# fram_rtc.net
KiCad netlist of a schematic drawn in Altium Designer
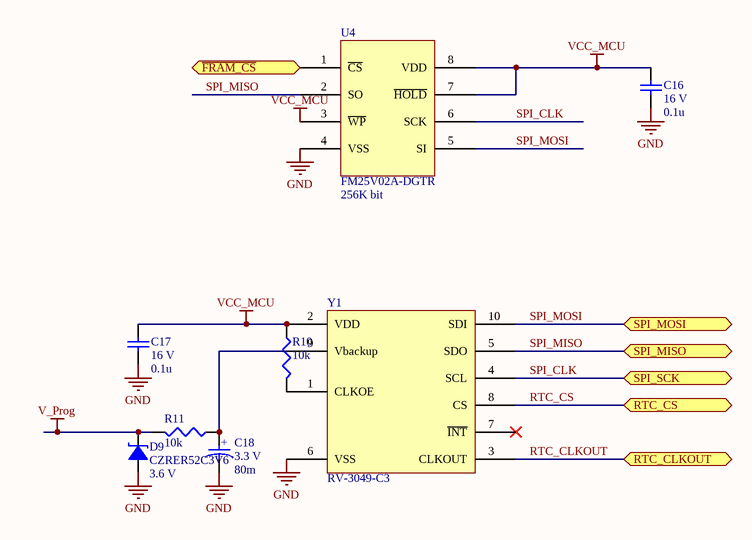
[diagram p0: fram_rtc.SchDoc]

(export (version "E")
  (design (tool "Eeschema 10.0.6"))
  (components
    (comp (ref "C16")
      (value "0.1u")
      (footprint "0402")
      (description "0.10µF ±10% 16V Ceramic Capacitor X7R 0402")
      (fields
        (field (name "VOLTAGE RATED") "16 V")
        (field (name "TOLERANCE") "10%")
        (field (name "MANUFACTURER PART NUMBER") "GRM155R71C104KA88D")
      )
      (libsource (lib "capacitors") (part "GRM155R71C104KA88D"))
    )
    (comp (ref "C17")
      (value "0.1u")
      (footprint "0402")
      (description "0.10µF ±10% 16V Ceramic Capacitor X7R 0402")
      (fields
        (field (name "VOLTAGE RATED") "16 V")
        (field (name "TOLERANCE") "10%")
        (field (name "MANUFACTURER PART NUMBER") "GRM155R71C104KA88D")
      )
      (libsource (lib "capacitors") (part "GRM155R71C104KA88D"))
    )
    (comp (ref "C18")
      (value "80m")
      (footprint "XH414HG-IV01E")
      (description "80mF (EDLC) Supercapacitor 3.3V Coin")
      (fields
        (field (name "VOLTAGE RATED") "3.3 V")
        (field (name "MANUFACTURER PART NUMBER") "XH414HG-IV01E")
      )
      (libsource (lib "capacitors") (part "XH414HG-IV01E"))
    )
    (comp (ref "D9")
      (value "CZRER52C3V6")
      (footprint "0503/SOD-723F")
      (description "Zener Diode 3.6V 150mW ±5% Surface Mount 0503 (1308 Metric)")
      (fields
        (field (name "MANUFACTURER") "Comchip Technology")
        (field (name "POWER") "150 mW")
        (field (name "ZENER VOLTAGE") "3.6 V")
      )
      (libsource (lib "diodes") (part "CZRER52C3V6"))
    )
    (comp (ref "R10")
      (value "10k")
      (footprint "0402")
      (description "RES SMD 10K OHM 1% 1/16W 0402")
      (fields (field (name "TOLERANCE") "1%") (field (name "POWER") "1/16 W"))
      (libsource (lib "resistors") (part "CRCW040210K0FKED"))
    )
    (comp (ref "R11")
      (value "10k")
      (footprint "0402")
      (description "RES SMD 10K OHM 1% 1/16W 0402")
      (fields (field (name "TOLERANCE") "1%") (field (name "POWER") "1/16 W"))
      (libsource (lib "resistors") (part "CRCW040210K0FKED"))
    )
    (comp (ref "U4")
      (value "FM25V02A-DGTR")
      (footprint "TDFN-8")
      (description "256-Kbit (32 K × 8) Serial (SPI) F-RAM")
      (fields (field (name "MANUFACTURER") "Cypress Semiconductor") (field (name "SIZE") "256K bit"))
      (libsource (lib "memory") (part "FM25V02A-DGTR"))
    )
    (comp (ref "Y1")
      (value "RV-3049-C3")
      (footprint "RV-3049-C3")
      (description "Real Time Clock Module with SPI-Bus")
      (libsource (lib "crystal oscillators") (part "RV-3049-C3"))
    )
  )
  (nets
    (net (code "1") (name "/RTC_CLKOUT") (class "Default")
      (node (ref "Y1") (pin "3") (pinfunction "CLKOUT_3") (pintype "passive"))
    )
    (net (code "2") (name "/RTC_CS") (class "Default")
      (node (ref "Y1") (pin "8") (pinfunction "CS_8") (pintype "passive"))
    )
    (net (code "3") (name "/SPI_CLK") (class "Default")
      (node (ref "U4") (pin "6") (pinfunction "SCK_6") (pintype "passive"))
      (node (ref "Y1") (pin "4") (pinfunction "SCL_4") (pintype "passive"))
    )
    (net (code "4") (name "/SPI_MISO") (class "Default")
      (node (ref "U4") (pin "2") (pinfunction "SO_2") (pintype "passive"))
      (node (ref "Y1") (pin "5") (pinfunction "SDO_5") (pintype "passive"))
    )
    (net (code "5") (name "/SPI_MOSI") (class "Default")
      (node (ref "U4") (pin "5") (pinfunction "SI_5") (pintype "passive"))
      (node (ref "Y1") (pin "10") (pinfunction "SDI_10") (pintype "passive"))
    )
    (net (code "6") (name "/~{FRAM_CS}") (class "Default")
      (node (ref "U4") (pin "1") (pinfunction "~{CS}_1") (pintype "passive"))
    )
    (net (code "7") (name "GND") (class "Default")
      (node (ref "C16") (pin "2") (pintype "passive"))
      (node (ref "C17") (pin "2") (pintype "passive"))
      (node (ref "C18") (pin "2") (pintype "passive"))
      (node (ref "D9") (pin "1") (pintype "passive"))
      (node (ref "U4") (pin "4") (pinfunction "VSS_4") (pintype "passive"))
      (node (ref "Y1") (pin "6") (pinfunction "VSS_6") (pintype "passive"))
    )
    (net (code "8") (name "Net-(Y1-CLKOE)") (class "Default")
      (node (ref "R10") (pin "1") (pintype "passive"))
      (node (ref "Y1") (pin "1") (pinfunction "CLKOE_1") (pintype "passive"))
    )
    (net (code "9") (name "Net-(Y1-Vbackup)") (class "Default")
      (node (ref "C18") (pin "1") (pintype "passive"))
      (node (ref "R11") (pin "2") (pintype "passive"))
      (node (ref "Y1") (pin "9") (pinfunction "Vbackup_9") (pintype "passive"))
    )
    (net (code "10") (name "VCC_MCU") (class "Default")
      (node (ref "C16") (pin "1") (pintype "passive"))
      (node (ref "C17") (pin "1") (pintype "passive"))
      (node (ref "R10") (pin "2") (pintype "passive"))
      (node (ref "U4") (pin "3") (pinfunction "~{WP}_3") (pintype "passive"))
      (node (ref "U4") (pin "7") (pinfunction "~{HOLD}_7") (pintype "passive"))
      (node (ref "U4") (pin "8") (pinfunction "VDD_8") (pintype "passive"))
      (node (ref "Y1") (pin "2") (pinfunction "VDD_2") (pintype "passive"))
    )
    (net (code "11") (name "V_Prog") (class "Default")
      (node (ref "D9") (pin "2") (pintype "passive"))
      (node (ref "R11") (pin "1") (pintype "passive"))
    )
    (net (code "12") (name "unconnected-(Y1-~{INT}-Pad7)") (class "Default")
      (node (ref "Y1") (pin "7") (pinfunction "~{INT}_7") (pintype "passive+no_connect"))
    )
  )
)
